# servo-shield.net
KiCad netlist of a schematic drawn in EAGLE
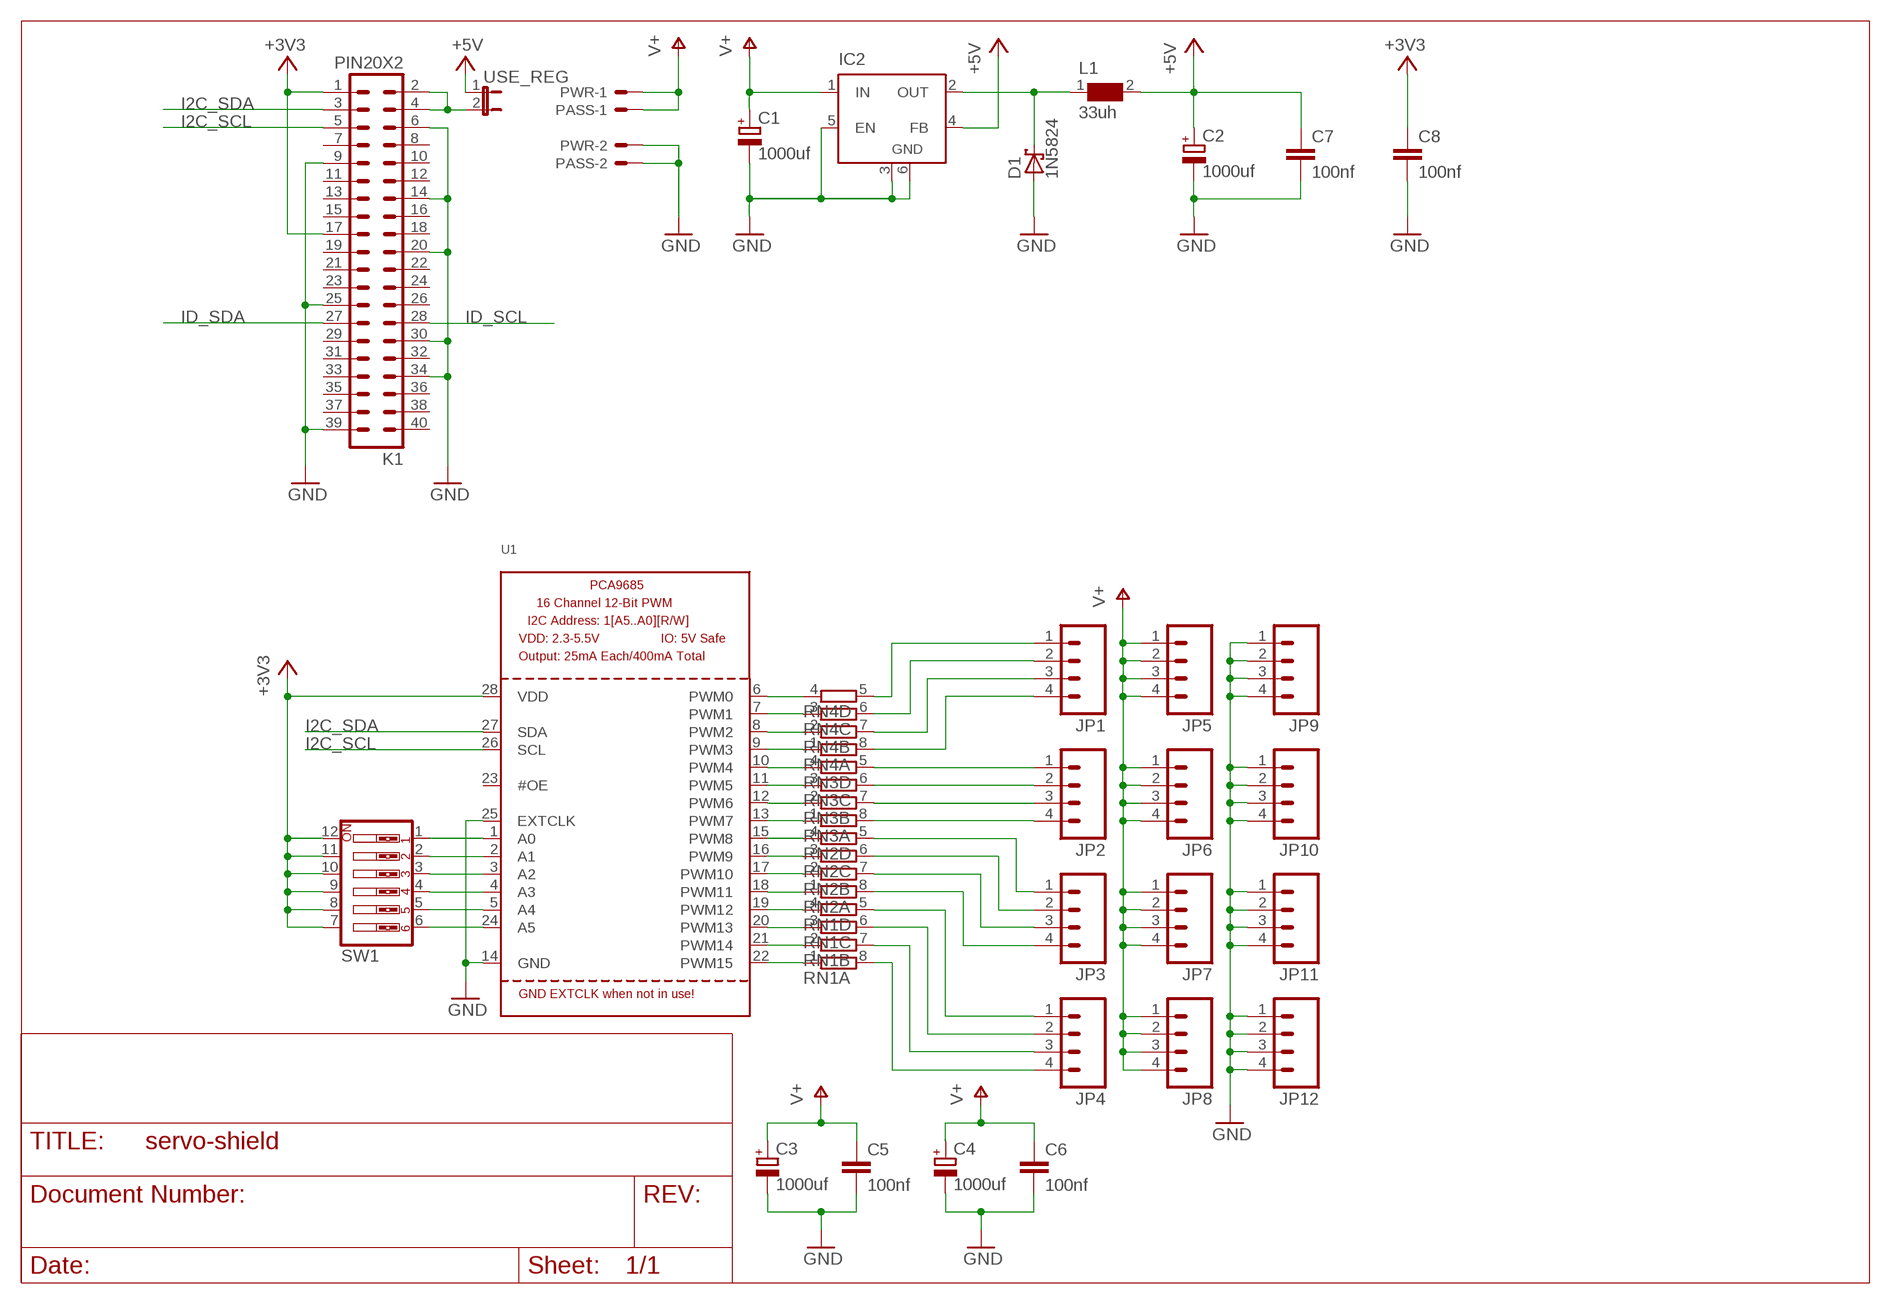
[diagram p0: schematic, sheet 1]

(export (version "E")
  (design (tool "Eeschema 10.0.6"))
  (components
    (comp (ref "C1")
      (value "1000uf")
      (footprint "eagle-import:E3,5-8")
      (libsource (lib "eagle-import") (part "CPOL-EUE3.5-8"))
    )
    (comp (ref "C2")
      (value "1000uf")
      (footprint "eagle-import:E3,5-8")
      (libsource (lib "eagle-import") (part "CPOL-EUE3.5-8"))
    )
    (comp (ref "C3")
      (value "1000uf")
      (footprint "eagle-import:E3,5-8")
      (libsource (lib "eagle-import") (part "CPOL-EUE3.5-8"))
    )
    (comp (ref "C4")
      (value "1000uf")
      (footprint "eagle-import:E3,5-8")
      (libsource (lib "eagle-import") (part "CPOL-EUE3.5-8"))
    )
    (comp (ref "C5")
      (value "100nf")
      (footprint "eagle-import:C025-030X050")
      (libsource (lib "eagle-import") (part "C-EU025-030X050"))
    )
    (comp (ref "C6")
      (value "100nf")
      (footprint "eagle-import:C025-030X050")
      (libsource (lib "eagle-import") (part "C-EU025-030X050"))
    )
    (comp (ref "C7")
      (value "100nf")
      (footprint "eagle-import:C025-030X050")
      (libsource (lib "eagle-import") (part "C-EU025-030X050"))
    )
    (comp (ref "C8")
      (value "100nf")
      (footprint "eagle-import:C025-030X050")
      (libsource (lib "eagle-import") (part "C-EU025-030X050"))
    )
    (comp (ref "D1")
      (value "1N5824")
      (footprint "eagle-import:DO41-7.6")
      (libsource (lib "eagle-import") (part "1N5817-B"))
    )
    (comp (ref "IC2")
      (value "LM2596S")
      (footprint "eagle-import:TO263-5")
      (libsource (lib "eagle-import") (part "LM2596S"))
    )
    (comp (ref "JP1")
      (value "M04LOCK")
      (footprint "eagle-import:1X04_LOCK")
      (libsource (lib "eagle-import") (part "M04LOCK"))
    )
    (comp (ref "JP2")
      (value "M04LOCK")
      (footprint "eagle-import:1X04_LOCK")
      (libsource (lib "eagle-import") (part "M04LOCK"))
    )
    (comp (ref "JP3")
      (value "M04LOCK")
      (footprint "eagle-import:1X04_LOCK")
      (libsource (lib "eagle-import") (part "M04LOCK"))
    )
    (comp (ref "JP4")
      (value "M04LOCK")
      (footprint "eagle-import:1X04_LOCK")
      (libsource (lib "eagle-import") (part "M04LOCK"))
    )
    (comp (ref "JP5")
      (value "M04LOCK")
      (footprint "eagle-import:1X04_LOCK")
      (libsource (lib "eagle-import") (part "M04LOCK"))
    )
    (comp (ref "JP6")
      (value "M04LOCK")
      (footprint "eagle-import:1X04_LOCK")
      (libsource (lib "eagle-import") (part "M04LOCK"))
    )
    (comp (ref "JP7")
      (value "M04LOCK")
      (footprint "eagle-import:1X04_LOCK")
      (libsource (lib "eagle-import") (part "M04LOCK"))
    )
    (comp (ref "JP8")
      (value "M04LOCK")
      (footprint "eagle-import:1X04_LOCK")
      (libsource (lib "eagle-import") (part "M04LOCK"))
    )
    (comp (ref "JP9")
      (value "M04LOCK")
      (footprint "eagle-import:1X04_LOCK")
      (libsource (lib "eagle-import") (part "M04LOCK"))
    )
    (comp (ref "JP10")
      (value "M04LOCK")
      (footprint "eagle-import:1X04_LOCK")
      (libsource (lib "eagle-import") (part "M04LOCK"))
    )
    (comp (ref "JP11")
      (value "M04LOCK")
      (footprint "eagle-import:1X04_LOCK")
      (libsource (lib "eagle-import") (part "M04LOCK"))
    )
    (comp (ref "JP12")
      (value "M04LOCK")
      (footprint "eagle-import:1X04_LOCK")
      (libsource (lib "eagle-import") (part "M04LOCK"))
    )
    (comp (ref "K1")
      (value "PIN20X2")
      (footprint "eagle-import:PIN_20X2")
      (libsource (lib "eagle-import") (part "PIN20X2"))
    )
    (comp (ref "L1")
      (value "33uh")
      (footprint "eagle-import:WE-PD_1260_1245_1280_1210")
      (fields (field (name "MPN") "744770133"))
      (libsource (lib "eagle-import") (part "WE-PD_1260/1245/1280/1210-744770133"))
    )
    (comp (ref "PASS")
      (value "22-05-7028-02")
      (footprint "eagle-import:7395-02")
      (libsource (lib "eagle-import") (part "22-?-0205-7028"))
    )
    (comp (ref "PWR")
      (value "22-05-7028-02")
      (footprint "eagle-import:7395-02")
      (libsource (lib "eagle-import") (part "22-?-0205-7028"))
    )
    (comp (ref "RN1")
      (value "4R-NEXB38V")
      (footprint "eagle-import:EXB38V")
      (libsource (lib "eagle-import") (part "4R-NEXB38V"))
    )
    (comp (ref "RN2")
      (value "4R-NEXB38V")
      (footprint "eagle-import:EXB38V")
      (libsource (lib "eagle-import") (part "4R-NEXB38V"))
    )
    (comp (ref "RN3")
      (value "4R-NEXB38V")
      (footprint "eagle-import:EXB38V")
      (libsource (lib "eagle-import") (part "4R-NEXB38V"))
    )
    (comp (ref "RN4")
      (value "4R-NEXB38V")
      (footprint "eagle-import:EXB38V")
      (libsource (lib "eagle-import") (part "4R-NEXB38V"))
    )
    (comp (ref "SW1")
      (value "SW_DIP-6")
      (footprint "eagle-import:EDG-06")
      (libsource (lib "eagle-import") (part "SW_DIP-6"))
    )
    (comp (ref "U1")
      (value "PCA9685")
      (footprint "eagle-import:TSSOP28")
      (libsource (lib "eagle-import") (part "PCA9685"))
    )
    (comp (ref "USE_REG")
      (value "JP1E")
      (footprint "eagle-import:JP1")
      (libsource (lib "eagle-import") (part "JP1E"))
    )
  )
  (nets
    (net (code "1") (name "+3V3") (class "Default")
      (node (ref "C8") (pin "1") (pinfunction "1_1") (pintype "passive"))
      (node (ref "K1") (pin "1") (pinfunction "1_1") (pintype "passive"))
      (node (ref "K1") (pin "17") (pinfunction "17_17") (pintype "passive"))
      (node (ref "SW1") (pin "10") (pinfunction "10_10") (pintype "passive"))
      (node (ref "SW1") (pin "11") (pinfunction "11_11") (pintype "passive"))
      (node (ref "SW1") (pin "12") (pinfunction "12_12") (pintype "passive"))
      (node (ref "SW1") (pin "7") (pinfunction "7_7") (pintype "passive"))
      (node (ref "SW1") (pin "8") (pinfunction "8_8") (pintype "passive"))
      (node (ref "SW1") (pin "9") (pinfunction "9_9") (pintype "passive"))
      (node (ref "U1") (pin "28") (pinfunction "VDD_28") (pintype "power_in"))
    )
    (net (code "2") (name "+5V") (class "Default")
      (node (ref "C2") (pin "+") (pinfunction "+_+") (pintype "passive"))
      (node (ref "C7") (pin "1") (pinfunction "1_1") (pintype "passive"))
      (node (ref "IC2") (pin "4") (pinfunction "FB_4") (pintype "input"))
      (node (ref "L1") (pin "2") (pinfunction "2_2") (pintype "passive"))
      (node (ref "USE_REG") (pin "1") (pinfunction "1_1") (pintype "passive"))
    )
    (net (code "3") (name "/I2C_SCL") (class "Default")
      (node (ref "K1") (pin "5") (pinfunction "5_5") (pintype "passive"))
      (node (ref "U1") (pin "26") (pinfunction "SCL_26") (pintype "bidirectional"))
    )
    (net (code "4") (name "/I2C_SDA") (class "Default")
      (node (ref "K1") (pin "3") (pinfunction "3_3") (pintype "passive"))
      (node (ref "U1") (pin "27") (pinfunction "SDA_27") (pintype "bidirectional"))
    )
    (net (code "5") (name "/ID_SCL") (class "Default")
      (node (ref "K1") (pin "28") (pinfunction "28_28") (pintype "passive"))
    )
    (net (code "6") (name "/ID_SDA") (class "Default")
      (node (ref "K1") (pin "27") (pinfunction "27_27") (pintype "passive"))
    )
    (net (code "7") (name "GND") (class "Default")
      (node (ref "C1") (pin "-") (pinfunction "-_-") (pintype "passive"))
      (node (ref "C2") (pin "-") (pinfunction "-_-") (pintype "passive"))
      (node (ref "C3") (pin "-") (pinfunction "-_-") (pintype "passive"))
      (node (ref "C4") (pin "-") (pinfunction "-_-") (pintype "passive"))
      (node (ref "C5") (pin "2") (pinfunction "2_2") (pintype "passive"))
      (node (ref "C6") (pin "2") (pinfunction "2_2") (pintype "passive"))
      (node (ref "C7") (pin "2") (pinfunction "2_2") (pintype "passive"))
      (node (ref "C8") (pin "2") (pinfunction "2_2") (pintype "passive"))
      (node (ref "D1") (pin "A") (pinfunction "A_A") (pintype "passive"))
      (node (ref "IC2") (pin "3") (pinfunction "GND_3") (pintype "power_in"))
      (node (ref "IC2") (pin "5") (pinfunction "EN_5") (pintype "input"))
      (node (ref "IC2") (pin "6") (pinfunction "GND_6") (pintype "power_in"))
      (node (ref "JP10") (pin "1") (pinfunction "1_1") (pintype "passive"))
      (node (ref "JP10") (pin "2") (pinfunction "2_2") (pintype "passive"))
      (node (ref "JP10") (pin "3") (pinfunction "3_3") (pintype "passive"))
      (node (ref "JP10") (pin "4") (pinfunction "4_4") (pintype "passive"))
      (node (ref "JP11") (pin "1") (pinfunction "1_1") (pintype "passive"))
      (node (ref "JP11") (pin "2") (pinfunction "2_2") (pintype "passive"))
      (node (ref "JP11") (pin "3") (pinfunction "3_3") (pintype "passive"))
      (node (ref "JP11") (pin "4") (pinfunction "4_4") (pintype "passive"))
      (node (ref "JP12") (pin "1") (pinfunction "1_1") (pintype "passive"))
      (node (ref "JP12") (pin "2") (pinfunction "2_2") (pintype "passive"))
      (node (ref "JP12") (pin "3") (pinfunction "3_3") (pintype "passive"))
      (node (ref "JP12") (pin "4") (pinfunction "4_4") (pintype "passive"))
      (node (ref "JP9") (pin "1") (pinfunction "1_1") (pintype "passive"))
      (node (ref "JP9") (pin "2") (pinfunction "2_2") (pintype "passive"))
      (node (ref "JP9") (pin "3") (pinfunction "3_3") (pintype "passive"))
      (node (ref "JP9") (pin "4") (pinfunction "4_4") (pintype "passive"))
      (node (ref "K1") (pin "14") (pinfunction "14_14") (pintype "passive"))
      (node (ref "K1") (pin "20") (pinfunction "20_20") (pintype "passive"))
      (node (ref "K1") (pin "25") (pinfunction "25_25") (pintype "passive"))
      (node (ref "K1") (pin "30") (pinfunction "30_30") (pintype "passive"))
      (node (ref "K1") (pin "34") (pinfunction "34_34") (pintype "passive"))
      (node (ref "K1") (pin "39") (pinfunction "39_39") (pintype "passive"))
      (node (ref "K1") (pin "6") (pinfunction "6_6") (pintype "passive"))
      (node (ref "K1") (pin "9") (pinfunction "9_9") (pintype "passive"))
      (node (ref "PASS") (pin "2") (pinfunction "S_2") (pintype "passive"))
      (node (ref "PWR") (pin "2") (pinfunction "S_2") (pintype "passive"))
      (node (ref "U1") (pin "14") (pinfunction "GND_14") (pintype "power_in"))
      (node (ref "U1") (pin "25") (pinfunction "EXTCLK_25") (pintype "input"))
    )
    (net (code "8") (name "Net-(IC2-OUT)") (class "Default")
      (node (ref "D1") (pin "C") (pinfunction "C_C") (pintype "passive"))
      (node (ref "IC2") (pin "2") (pinfunction "OUT_2") (pintype "output"))
      (node (ref "L1") (pin "1") (pinfunction "1_1") (pintype "passive"))
    )
    (net (code "9") (name "Net-(K1-Pad2)") (class "Default")
      (node (ref "K1") (pin "2") (pinfunction "2_2") (pintype "passive"))
      (node (ref "K1") (pin "4") (pinfunction "4_4") (pintype "passive"))
      (node (ref "USE_REG") (pin "2") (pinfunction "2_2") (pintype "passive"))
    )
    (net (code "10") (name "Net-(RN1A-2)") (class "Default")
      (node (ref "JP4") (pin "4") (pinfunction "4_4") (pintype "passive"))
      (node (ref "RN1") (pin "8") (pinfunction "2_8") (pintype "passive"))
    )
    (net (code "11") (name "Net-(RN1B-1)") (class "Default")
      (node (ref "RN1") (pin "2") (pinfunction "1_2") (pintype "passive"))
      (node (ref "U1") (pin "21") (pinfunction "PWM14_21") (pintype "output"))
    )
    (net (code "12") (name "Net-(RN1B-2)") (class "Default")
      (node (ref "JP4") (pin "3") (pinfunction "3_3") (pintype "passive"))
      (node (ref "RN1") (pin "7") (pinfunction "2_7") (pintype "passive"))
    )
    (net (code "13") (name "Net-(RN1C-1)") (class "Default")
      (node (ref "RN1") (pin "3") (pinfunction "1_3") (pintype "passive"))
      (node (ref "U1") (pin "20") (pinfunction "PWM13_20") (pintype "output"))
    )
    (net (code "14") (name "Net-(RN1C-2)") (class "Default")
      (node (ref "JP4") (pin "2") (pinfunction "2_2") (pintype "passive"))
      (node (ref "RN1") (pin "6") (pinfunction "2_6") (pintype "passive"))
    )
    (net (code "15") (name "Net-(RN1D-1)") (class "Default")
      (node (ref "RN1") (pin "4") (pinfunction "1_4") (pintype "passive"))
      (node (ref "U1") (pin "19") (pinfunction "PWM12_19") (pintype "output"))
    )
    (net (code "16") (name "Net-(RN1D-2)") (class "Default")
      (node (ref "JP4") (pin "1") (pinfunction "1_1") (pintype "passive"))
      (node (ref "RN1") (pin "5") (pinfunction "2_5") (pintype "passive"))
    )
    (net (code "17") (name "Net-(RN2A-2)") (class "Default")
      (node (ref "JP3") (pin "4") (pinfunction "4_4") (pintype "passive"))
      (node (ref "RN2") (pin "8") (pinfunction "2_8") (pintype "passive"))
    )
    (net (code "18") (name "Net-(RN2B-1)") (class "Default")
      (node (ref "RN2") (pin "2") (pinfunction "1_2") (pintype "passive"))
      (node (ref "U1") (pin "17") (pinfunction "PWM10_17") (pintype "output"))
    )
    (net (code "19") (name "Net-(RN2B-2)") (class "Default")
      (node (ref "JP3") (pin "3") (pinfunction "3_3") (pintype "passive"))
      (node (ref "RN2") (pin "7") (pinfunction "2_7") (pintype "passive"))
    )
    (net (code "20") (name "Net-(RN2C-1)") (class "Default")
      (node (ref "RN2") (pin "3") (pinfunction "1_3") (pintype "passive"))
      (node (ref "U1") (pin "16") (pinfunction "PWM9_16") (pintype "output"))
    )
    (net (code "21") (name "Net-(RN2C-2)") (class "Default")
      (node (ref "JP3") (pin "2") (pinfunction "2_2") (pintype "passive"))
      (node (ref "RN2") (pin "6") (pinfunction "2_6") (pintype "passive"))
    )
    (net (code "22") (name "Net-(RN2D-1)") (class "Default")
      (node (ref "RN2") (pin "4") (pinfunction "1_4") (pintype "passive"))
      (node (ref "U1") (pin "15") (pinfunction "PWM8_15") (pintype "output"))
    )
    (net (code "23") (name "Net-(RN2D-2)") (class "Default")
      (node (ref "JP3") (pin "1") (pinfunction "1_1") (pintype "passive"))
      (node (ref "RN2") (pin "5") (pinfunction "2_5") (pintype "passive"))
    )
    (net (code "24") (name "Net-(RN3A-2)") (class "Default")
      (node (ref "JP2") (pin "4") (pinfunction "4_4") (pintype "passive"))
      (node (ref "RN3") (pin "8") (pinfunction "2_8") (pintype "passive"))
    )
    (net (code "25") (name "Net-(RN3B-1)") (class "Default")
      (node (ref "RN3") (pin "2") (pinfunction "1_2") (pintype "passive"))
      (node (ref "U1") (pin "12") (pinfunction "PWM6_12") (pintype "output"))
    )
    (net (code "26") (name "Net-(RN3B-2)") (class "Default")
      (node (ref "JP2") (pin "3") (pinfunction "3_3") (pintype "passive"))
      (node (ref "RN3") (pin "7") (pinfunction "2_7") (pintype "passive"))
    )
    (net (code "27") (name "Net-(RN3C-1)") (class "Default")
      (node (ref "RN3") (pin "3") (pinfunction "1_3") (pintype "passive"))
      (node (ref "U1") (pin "11") (pinfunction "PWM5_11") (pintype "output"))
    )
    (net (code "28") (name "Net-(RN3C-2)") (class "Default")
      (node (ref "JP2") (pin "2") (pinfunction "2_2") (pintype "passive"))
      (node (ref "RN3") (pin "6") (pinfunction "2_6") (pintype "passive"))
    )
    (net (code "29") (name "Net-(RN3D-1)") (class "Default")
      (node (ref "RN3") (pin "4") (pinfunction "1_4") (pintype "passive"))
      (node (ref "U1") (pin "10") (pinfunction "PWM4_10") (pintype "output"))
    )
    (net (code "30") (name "Net-(RN3D-2)") (class "Default")
      (node (ref "JP2") (pin "1") (pinfunction "1_1") (pintype "passive"))
      (node (ref "RN3") (pin "5") (pinfunction "2_5") (pintype "passive"))
    )
    (net (code "31") (name "Net-(RN4A-2)") (class "Default")
      (node (ref "JP1") (pin "4") (pinfunction "4_4") (pintype "passive"))
      (node (ref "RN4") (pin "8") (pinfunction "2_8") (pintype "passive"))
    )
    (net (code "32") (name "Net-(RN4B-1)") (class "Default")
      (node (ref "RN4") (pin "2") (pinfunction "1_2") (pintype "passive"))
      (node (ref "U1") (pin "8") (pinfunction "PWM2_8") (pintype "output"))
    )
    (net (code "33") (name "Net-(RN4B-2)") (class "Default")
      (node (ref "JP1") (pin "3") (pinfunction "3_3") (pintype "passive"))
      (node (ref "RN4") (pin "7") (pinfunction "2_7") (pintype "passive"))
    )
    (net (code "34") (name "Net-(RN4C-1)") (class "Default")
      (node (ref "RN4") (pin "3") (pinfunction "1_3") (pintype "passive"))
      (node (ref "U1") (pin "7") (pinfunction "PWM1_7") (pintype "output"))
    )
    (net (code "35") (name "Net-(RN4C-2)") (class "Default")
      (node (ref "JP1") (pin "2") (pinfunction "2_2") (pintype "passive"))
      (node (ref "RN4") (pin "6") (pinfunction "2_6") (pintype "passive"))
    )
    (net (code "36") (name "Net-(RN4D-1)") (class "Default")
      (node (ref "RN4") (pin "4") (pinfunction "1_4") (pintype "passive"))
      (node (ref "U1") (pin "6") (pinfunction "PWM0_6") (pintype "output"))
    )
    (net (code "37") (name "Net-(RN4D-2)") (class "Default")
      (node (ref "JP1") (pin "1") (pinfunction "1_1") (pintype "passive"))
      (node (ref "RN4") (pin "5") (pinfunction "2_5") (pintype "passive"))
    )
    (net (code "38") (name "Net-(U1-A0)") (class "Default")
      (node (ref "SW1") (pin "1") (pinfunction "1_1") (pintype "passive"))
      (node (ref "U1") (pin "1") (pinfunction "A0_1") (pintype "bidirectional"))
    )
    (net (code "39") (name "Net-(U1-A1)") (class "Default")
      (node (ref "SW1") (pin "2") (pinfunction "2_2") (pintype "passive"))
      (node (ref "U1") (pin "2") (pinfunction "A1_2") (pintype "bidirectional"))
    )
    (net (code "40") (name "Net-(U1-A2)") (class "Default")
      (node (ref "SW1") (pin "3") (pinfunction "3_3") (pintype "passive"))
      (node (ref "U1") (pin "3") (pinfunction "A2_3") (pintype "bidirectional"))
    )
    (net (code "41") (name "Net-(U1-A3)") (class "Default")
      (node (ref "SW1") (pin "4") (pinfunction "4_4") (pintype "passive"))
      (node (ref "U1") (pin "4") (pinfunction "A3_4") (pintype "bidirectional"))
    )
    (net (code "42") (name "Net-(U1-A4)") (class "Default")
      (node (ref "SW1") (pin "5") (pinfunction "5_5") (pintype "passive"))
      (node (ref "U1") (pin "5") (pinfunction "A4_5") (pintype "bidirectional"))
    )
    (net (code "43") (name "Net-(U1-A5)") (class "Default")
      (node (ref "SW1") (pin "6") (pinfunction "6_6") (pintype "passive"))
      (node (ref "U1") (pin "24") (pinfunction "A5_24") (pintype "bidirectional"))
    )
    (net (code "44") (name "Net-(U1-PWM3)") (class "Default")
      (node (ref "RN4") (pin "1") (pinfunction "1_1") (pintype "passive"))
      (node (ref "U1") (pin "9") (pinfunction "PWM3_9") (pintype "output"))
    )
    (net (code "45") (name "Net-(U1-PWM7)") (class "Default")
      (node (ref "RN3") (pin "1") (pinfunction "1_1") (pintype "passive"))
      (node (ref "U1") (pin "13") (pinfunction "PWM7_13") (pintype "output"))
    )
    (net (code "46") (name "Net-(U1-PWM11)") (class "Default")
      (node (ref "RN2") (pin "1") (pinfunction "1_1") (pintype "passive"))
      (node (ref "U1") (pin "18") (pinfunction "PWM11_18") (pintype "output"))
    )
    (net (code "47") (name "Net-(U1-PWM15)") (class "Default")
      (node (ref "RN1") (pin "1") (pinfunction "1_1") (pintype "passive"))
      (node (ref "U1") (pin "22") (pinfunction "PWM15_22") (pintype "output"))
    )
    (net (code "48") (name "V+") (class "Default")
      (node (ref "C1") (pin "+") (pinfunction "+_+") (pintype "passive"))
      (node (ref "C3") (pin "+") (pinfunction "+_+") (pintype "passive"))
      (node (ref "C4") (pin "+") (pinfunction "+_+") (pintype "passive"))
      (node (ref "C5") (pin "1") (pinfunction "1_1") (pintype "passive"))
      (node (ref "C6") (pin "1") (pinfunction "1_1") (pintype "passive"))
      (node (ref "IC2") (pin "1") (pinfunction "IN_1") (pintype "input"))
      (node (ref "JP5") (pin "1") (pinfunction "1_1") (pintype "passive"))
      (node (ref "JP5") (pin "2") (pinfunction "2_2") (pintype "passive"))
      (node (ref "JP5") (pin "3") (pinfunction "3_3") (pintype "passive"))
      (node (ref "JP5") (pin "4") (pinfunction "4_4") (pintype "passive"))
      (node (ref "JP6") (pin "1") (pinfunction "1_1") (pintype "passive"))
      (node (ref "JP6") (pin "2") (pinfunction "2_2") (pintype "passive"))
      (node (ref "JP6") (pin "3") (pinfunction "3_3") (pintype "passive"))
      (node (ref "JP6") (pin "4") (pinfunction "4_4") (pintype "passive"))
      (node (ref "JP7") (pin "1") (pinfunction "1_1") (pintype "passive"))
      (node (ref "JP7") (pin "2") (pinfunction "2_2") (pintype "passive"))
      (node (ref "JP7") (pin "3") (pinfunction "3_3") (pintype "passive"))
      (node (ref "JP7") (pin "4") (pinfunction "4_4") (pintype "passive"))
      (node (ref "JP8") (pin "1") (pinfunction "1_1") (pintype "passive"))
      (node (ref "JP8") (pin "2") (pinfunction "2_2") (pintype "passive"))
      (node (ref "JP8") (pin "3") (pinfunction "3_3") (pintype "passive"))
      (node (ref "JP8") (pin "4") (pinfunction "4_4") (pintype "passive"))
      (node (ref "PASS") (pin "1") (pinfunction "S_1") (pintype "passive"))
      (node (ref "PWR") (pin "1") (pinfunction "S_1") (pintype "passive"))
    )
    (net (code "49") (name "unconnected-(K1-Pad7)") (class "Default")
      (node (ref "K1") (pin "7") (pinfunction "7_7") (pintype "passive"))
    )
    (net (code "50") (name "unconnected-(K1-Pad8)") (class "Default")
      (node (ref "K1") (pin "8") (pinfunction "8_8") (pintype "passive"))
    )
    (net (code "51") (name "unconnected-(K1-Pad10)") (class "Default")
      (node (ref "K1") (pin "10") (pinfunction "10_10") (pintype "passive"))
    )
    (net (code "52") (name "unconnected-(K1-Pad11)") (class "Default")
      (node (ref "K1") (pin "11") (pinfunction "11_11") (pintype "passive"))
    )
    (net (code "53") (name "unconnected-(K1-Pad12)") (class "Default")
      (node (ref "K1") (pin "12") (pinfunction "12_12") (pintype "passive"))
    )
    (net (code "54") (name "unconnected-(K1-Pad13)") (class "Default")
      (node (ref "K1") (pin "13") (pinfunction "13_13") (pintype "passive"))
    )
    (net (code "55") (name "unconnected-(K1-Pad15)") (class "Default")
      (node (ref "K1") (pin "15") (pinfunction "15_15") (pintype "passive"))
    )
    (net (code "56") (name "unconnected-(K1-Pad16)") (class "Default")
      (node (ref "K1") (pin "16") (pinfunction "16_16") (pintype "passive"))
    )
    (net (code "57") (name "unconnected-(K1-Pad18)") (class "Default")
      (node (ref "K1") (pin "18") (pinfunction "18_18") (pintype "passive"))
    )
    (net (code "58") (name "unconnected-(K1-Pad19)") (class "Default")
      (node (ref "K1") (pin "19") (pinfunction "19_19") (pintype "passive"))
    )
    (net (code "59") (name "unconnected-(K1-Pad21)") (class "Default")
      (node (ref "K1") (pin "21") (pinfunction "21_21") (pintype "passive"))
    )
    (net (code "60") (name "unconnected-(K1-Pad22)") (class "Default")
      (node (ref "K1") (pin "22") (pinfunction "22_22") (pintype "passive"))
    )
    (net (code "61") (name "unconnected-(K1-Pad23)") (class "Default")
      (node (ref "K1") (pin "23") (pinfunction "23_23") (pintype "passive"))
    )
    (net (code "62") (name "unconnected-(K1-Pad24)") (class "Default")
      (node (ref "K1") (pin "24") (pinfunction "24_24") (pintype "passive"))
    )
    (net (code "63") (name "unconnected-(K1-Pad26)") (class "Default")
      (node (ref "K1") (pin "26") (pinfunction "26_26") (pintype "passive"))
    )
    (net (code "64") (name "unconnected-(K1-Pad29)") (class "Default")
      (node (ref "K1") (pin "29") (pinfunction "29_29") (pintype "passive"))
    )
    (net (code "65") (name "unconnected-(K1-Pad31)") (class "Default")
      (node (ref "K1") (pin "31") (pinfunction "31_31") (pintype "passive"))
    )
    (net (code "66") (name "unconnected-(K1-Pad32)") (class "Default")
      (node (ref "K1") (pin "32") (pinfunction "32_32") (pintype "passive"))
    )
    (net (code "67") (name "unconnected-(K1-Pad33)") (class "Default")
      (node (ref "K1") (pin "33") (pinfunction "33_33") (pintype "passive"))
    )
    (net (code "68") (name "unconnected-(K1-Pad35)") (class "Default")
      (node (ref "K1") (pin "35") (pinfunction "35_35") (pintype "passive"))
    )
    (net (code "69") (name "unconnected-(K1-Pad36)") (class "Default")
      (node (ref "K1") (pin "36") (pinfunction "36_36") (pintype "passive"))
    )
    (net (code "70") (name "unconnected-(K1-Pad37)") (class "Default")
      (node (ref "K1") (pin "37") (pinfunction "37_37") (pintype "passive"))
    )
    (net (code "71") (name "unconnected-(K1-Pad38)") (class "Default")
      (node (ref "K1") (pin "38") (pinfunction "38_38") (pintype "passive"))
    )
    (net (code "72") (name "unconnected-(K1-Pad40)") (class "Default")
      (node (ref "K1") (pin "40") (pinfunction "40_40") (pintype "passive"))
    )
    (net (code "73") (name "unconnected-(U1-#OE-Pad23)") (class "Default")
      (node (ref "U1") (pin "23") (pinfunction "#OE_23") (pintype "input"))
    )
  )
)
